# PowerAmpTDA2005.net
KiCad netlist of a schematic drawn in EAGLE
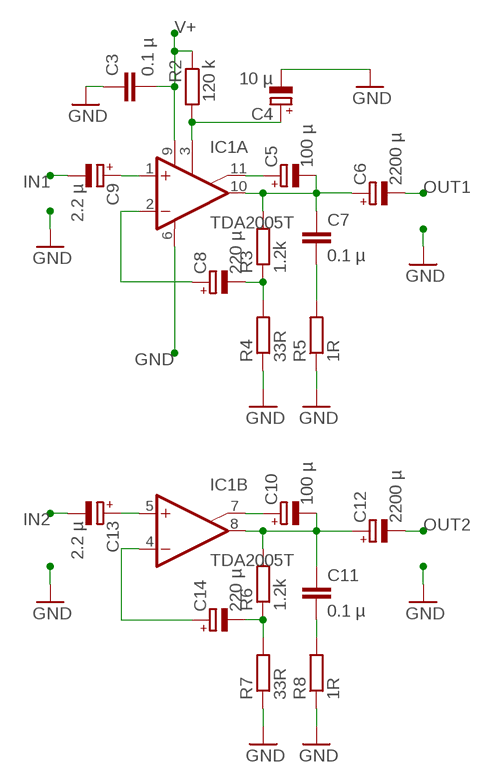
[diagram p0: schematic, sheet 1]

(export (version "E")
  (design (tool "Eeschema 10.0.6"))
  (components
    (comp (ref "C3")
      (value "0.1 µ")
      (footprint "eagle-import:C075-042X103")
      (libsource (lib "eagle-import") (part "C-EU075-042X103"))
    )
    (comp (ref "C4")
      (value "10 µ")
      (footprint "eagle-import:E2,5-5")
      (libsource (lib "eagle-import") (part "CPOL-EUE2.5-5"))
    )
    (comp (ref "C5")
      (value "100 µ")
      (footprint "eagle-import:E3,5-8")
      (libsource (lib "eagle-import") (part "CPOL-EUE3.5-8"))
    )
    (comp (ref "C6")
      (value "2200 µ")
      (footprint "eagle-import:E5-13")
      (libsource (lib "eagle-import") (part "CPOL-EUE5-13"))
    )
    (comp (ref "C7")
      (value "0.1 µ")
      (footprint "eagle-import:C075-042X103")
      (libsource (lib "eagle-import") (part "C-EU075-042X103"))
    )
    (comp (ref "C8")
      (value "220 µ")
      (footprint "eagle-import:E25-10")
      (libsource (lib "eagle-import") (part "CPOL-EUE25-10AXIAL"))
    )
    (comp (ref "C9")
      (value "2.2 µ")
      (footprint "eagle-import:E2-5")
      (libsource (lib "eagle-import") (part "CPOL-EUE2-5"))
    )
    (comp (ref "C10")
      (value "100 µ")
      (footprint "eagle-import:E3,5-8")
      (libsource (lib "eagle-import") (part "CPOL-EUE3.5-8"))
    )
    (comp (ref "C11")
      (value "0.1 µ")
      (footprint "eagle-import:C075-042X103")
      (libsource (lib "eagle-import") (part "C-EU075-042X103"))
    )
    (comp (ref "C12")
      (value "2200 µ")
      (footprint "eagle-import:E5-13")
      (libsource (lib "eagle-import") (part "CPOL-EUE5-13"))
    )
    (comp (ref "C13")
      (value "2.2 µ")
      (footprint "eagle-import:E2-5")
      (libsource (lib "eagle-import") (part "CPOL-EUE2-5"))
    )
    (comp (ref "C14")
      (value "220 µ")
      (footprint "eagle-import:E25-10")
      (libsource (lib "eagle-import") (part "CPOL-EUE25-10AXIAL"))
    )
    (comp (ref "IC1")
      (value "TDA2005T")
      (footprint "eagle-import:SIP11")
      (libsource (lib "eagle-import") (part "TDA2005T"))
    )
    (comp (ref "R2")
      (value "120 k")
      (footprint "eagle-import:0207_12")
      (libsource (lib "eagle-import") (part "R-EU_0207/12"))
    )
    (comp (ref "R3")
      (value "1.2k")
      (footprint "eagle-import:0207_12")
      (libsource (lib "eagle-import") (part "R-EU_0207/12"))
    )
    (comp (ref "R4")
      (value "33R")
      (footprint "eagle-import:0207_12")
      (libsource (lib "eagle-import") (part "R-EU_0207/12"))
    )
    (comp (ref "R5")
      (value "1R")
      (footprint "eagle-import:0207_12")
      (libsource (lib "eagle-import") (part "R-EU_0207/12"))
    )
    (comp (ref "R6")
      (value "1.2k")
      (footprint "eagle-import:0207_12")
      (libsource (lib "eagle-import") (part "R-EU_0207/12"))
    )
    (comp (ref "R7")
      (value "33R")
      (footprint "eagle-import:0207_12")
      (libsource (lib "eagle-import") (part "R-EU_0207/12"))
    )
    (comp (ref "R8")
      (value "1R")
      (footprint "eagle-import:0207_12")
      (libsource (lib "eagle-import") (part "R-EU_0207/12"))
    )
  )
  (nets
    (net (code "1") (name "/IN1") (class "Default")
      (node (ref "C9") (pin "-") (pinfunction "-_-") (pintype "passive"))
    )
    (net (code "2") (name "/IN2") (class "Default")
      (node (ref "C13") (pin "-") (pinfunction "-_-") (pintype "passive"))
    )
    (net (code "3") (name "/OUT1") (class "Default")
      (node (ref "C6") (pin "-") (pinfunction "-_-") (pintype "passive"))
    )
    (net (code "4") (name "/OUT2") (class "Default")
      (node (ref "C12") (pin "-") (pinfunction "-_-") (pintype "passive"))
    )
    (net (code "5") (name "/V+") (class "Default")
      (node (ref "C3") (pin "2") (pinfunction "2_2") (pintype "passive"))
      (node (ref "IC1") (pin "9") (pinfunction "V+_9") (pintype "power_in"))
      (node (ref "R2") (pin "1") (pinfunction "1_1") (pintype "passive"))
    )
    (net (code "6") (name "GND") (class "Default")
      (node (ref "C3") (pin "1") (pinfunction "1_1") (pintype "passive"))
      (node (ref "C4") (pin "-") (pinfunction "-_-") (pintype "passive"))
      (node (ref "IC1") (pin "6") (pinfunction "GND_6") (pintype "power_in"))
      (node (ref "R4") (pin "1") (pinfunction "1_1") (pintype "passive"))
      (node (ref "R5") (pin "1") (pinfunction "1_1") (pintype "passive"))
      (node (ref "R7") (pin "1") (pinfunction "1_1") (pintype "passive"))
      (node (ref "R8") (pin "1") (pinfunction "1_1") (pintype "passive"))
    )
    (net (code "7") (name "Net-(C7-Pad2)") (class "Default")
      (node (ref "C7") (pin "2") (pinfunction "2_2") (pintype "passive"))
      (node (ref "R5") (pin "2") (pinfunction "2_2") (pintype "passive"))
    )
    (net (code "8") (name "Net-(C8-Pad-)") (class "Default")
      (node (ref "C8") (pin "-") (pinfunction "-_-") (pintype "passive"))
      (node (ref "R3") (pin "1") (pinfunction "1_1") (pintype "passive"))
      (node (ref "R4") (pin "2") (pinfunction "2_2") (pintype "passive"))
    )
    (net (code "9") (name "Net-(C11-Pad2)") (class "Default")
      (node (ref "C11") (pin "2") (pinfunction "2_2") (pintype "passive"))
      (node (ref "R8") (pin "2") (pinfunction "2_2") (pintype "passive"))
    )
    (net (code "10") (name "Net-(C14-Pad-)") (class "Default")
      (node (ref "C14") (pin "-") (pinfunction "-_-") (pintype "passive"))
      (node (ref "R6") (pin "1") (pinfunction "1_1") (pintype "passive"))
      (node (ref "R7") (pin "2") (pinfunction "2_2") (pintype "passive"))
    )
    (net (code "11") (name "Net-(IC1A-+IN)") (class "Default")
      (node (ref "C9") (pin "+") (pinfunction "+_+") (pintype "passive"))
      (node (ref "IC1") (pin "1") (pinfunction "+IN_1") (pintype "input"))
    )
    (net (code "12") (name "Net-(IC1A--IN)") (class "Default")
      (node (ref "C8") (pin "+") (pinfunction "+_+") (pintype "passive"))
      (node (ref "IC1") (pin "2") (pinfunction "-IN_2") (pintype "input"))
    )
    (net (code "13") (name "Net-(IC1A-BTSP)") (class "Default")
      (node (ref "C5") (pin "+") (pinfunction "+_+") (pintype "passive"))
      (node (ref "IC1") (pin "11") (pinfunction "BTSP_11") (pintype "passive"))
    )
    (net (code "14") (name "Net-(IC1A-OUT)") (class "Default")
      (node (ref "C5") (pin "-") (pinfunction "-_-") (pintype "passive"))
      (node (ref "C6") (pin "+") (pinfunction "+_+") (pintype "passive"))
      (node (ref "C7") (pin "1") (pinfunction "1_1") (pintype "passive"))
      (node (ref "IC1") (pin "10") (pinfunction "OUT_10") (pintype "output"))
      (node (ref "R3") (pin "2") (pinfunction "2_2") (pintype "passive"))
    )
    (net (code "15") (name "Net-(IC1A-SVRR)") (class "Default")
      (node (ref "C4") (pin "+") (pinfunction "+_+") (pintype "passive"))
      (node (ref "IC1") (pin "3") (pinfunction "SVRR_3") (pintype "passive"))
      (node (ref "R2") (pin "2") (pinfunction "2_2") (pintype "passive"))
    )
    (net (code "16") (name "Net-(IC1B-+IN)") (class "Default")
      (node (ref "C13") (pin "+") (pinfunction "+_+") (pintype "passive"))
      (node (ref "IC1") (pin "5") (pinfunction "+IN_5") (pintype "input"))
    )
    (net (code "17") (name "Net-(IC1B--IN)") (class "Default")
      (node (ref "C14") (pin "+") (pinfunction "+_+") (pintype "passive"))
      (node (ref "IC1") (pin "4") (pinfunction "-IN_4") (pintype "input"))
    )
    (net (code "18") (name "Net-(IC1B-BTSP)") (class "Default")
      (node (ref "C10") (pin "+") (pinfunction "+_+") (pintype "passive"))
      (node (ref "IC1") (pin "7") (pinfunction "BTSP_7") (pintype "passive"))
    )
    (net (code "19") (name "Net-(IC1B-OUT)") (class "Default")
      (node (ref "C10") (pin "-") (pinfunction "-_-") (pintype "passive"))
      (node (ref "C11") (pin "1") (pinfunction "1_1") (pintype "passive"))
      (node (ref "C12") (pin "+") (pinfunction "+_+") (pintype "passive"))
      (node (ref "IC1") (pin "8") (pinfunction "OUT_8") (pintype "output"))
      (node (ref "R6") (pin "2") (pinfunction "2_2") (pintype "passive"))
    )
  )
)
